# Sheet1-IR-Sensor.net
KiCad netlist of a schematic drawn in Altium Designer
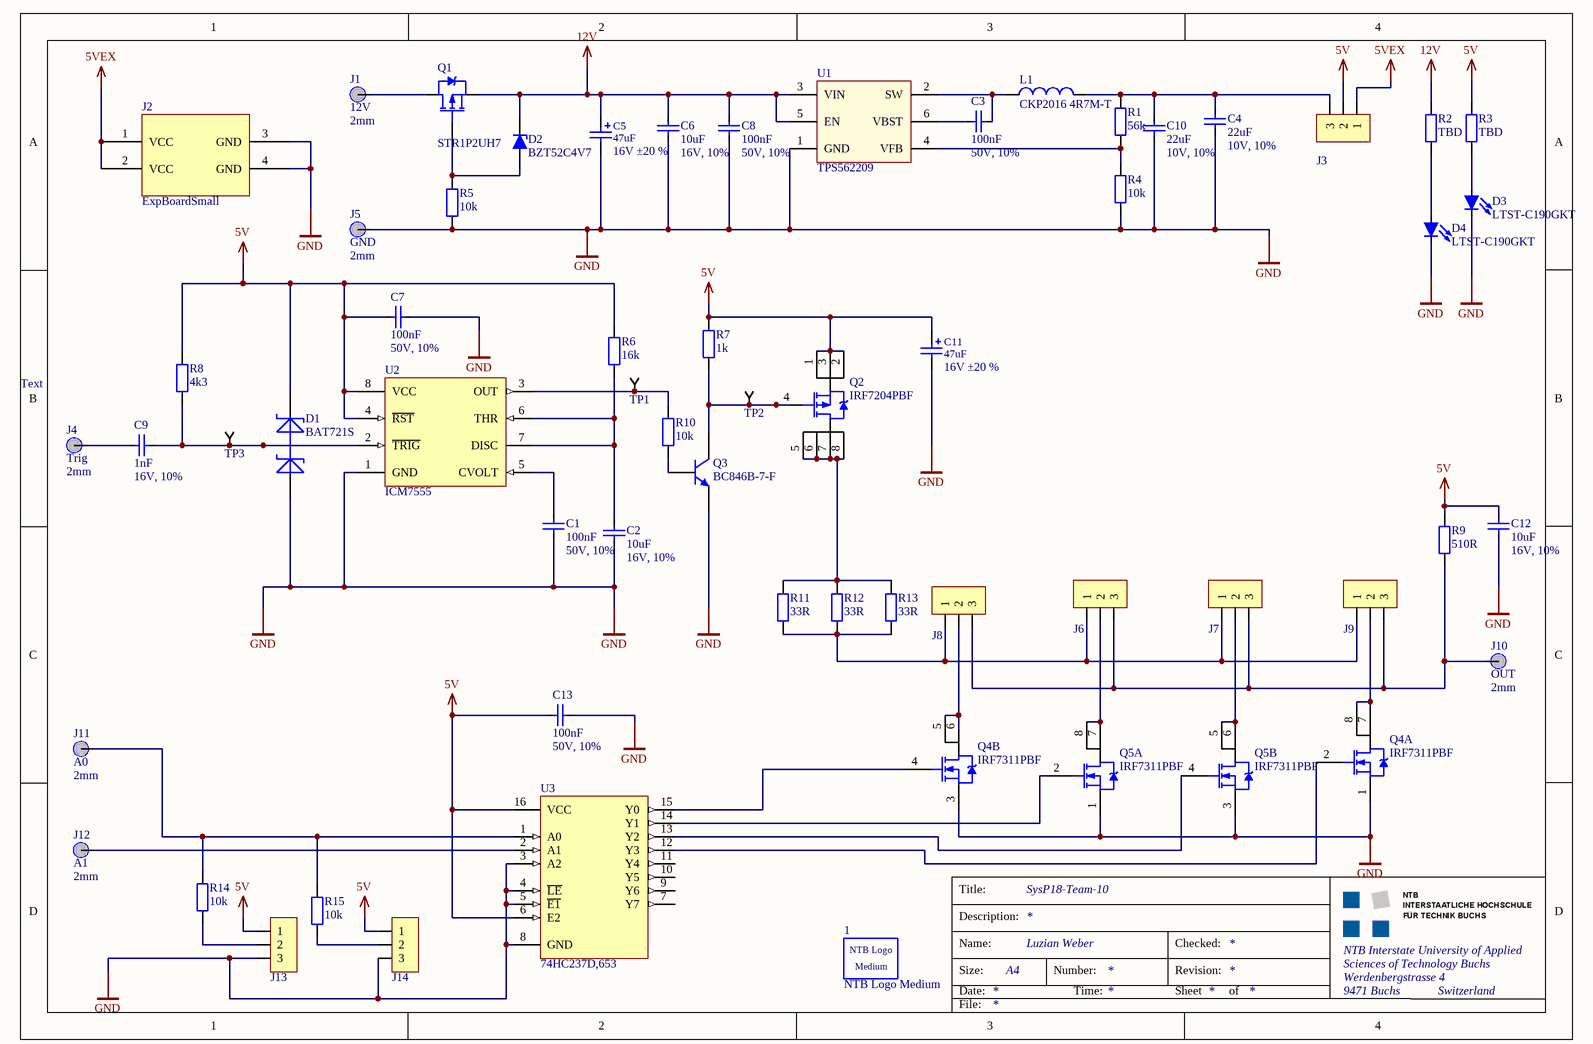
[diagram p0: Sheet1-IR-Sensor.SchDoc]

(export (version "E")
  (design (tool "Eeschema 10.0.6"))
  (components
    (comp (ref "1")
      (value "NTB Logo Medium")
      (footprint "NTB Logo Medium Copper")
      (libsource (lib "IR-Sensor") (part "NTB Logo Medium Copper"))
    )
    (comp (ref "C1")
      (value "100nF")
      (footprint "CAP-0805[2012]")
      (description "100n 50V X7R MLCC 0805 (1608 Metric)")
      (fields (field (name "TOLERANCE") "10%") (field (name "VALADDON") "50V, 10%"))
      (libsource (lib "IR-Sensor") (part "MLCC 0805 100n 50V"))
    )
    (comp (ref "C2")
      (value "10uF")
      (footprint "CAP-1206[3216]")
      (description "10u 16V X7R MLCC 1206 (3016 Metric)")
      (fields (field (name "TOLERANCE") "10%") (field (name "VALADDON") "16V, 10%"))
      (libsource (lib "IR-Sensor") (part "MLCC 1206 10u 16V"))
    )
    (comp (ref "C3")
      (value "100nF")
      (footprint "CAP-0805[2012]")
      (description "100n 50V X7R MLCC 0805 (1608 Metric)")
      (fields (field (name "TOLERANCE") "10%") (field (name "VALADDON") "50V, 10%"))
      (libsource (lib "IR-Sensor") (part "MLCC 0805 100n 50V"))
    )
    (comp (ref "C4")
      (value "22uF")
      (footprint "CAP-1206[3216]")
      (description "22u 10V X7R MLCC 1206 (3016 Metric)")
      (fields (field (name "TOLERANCE") "10%") (field (name "VALADDON") "10V, 10%"))
      (libsource (lib "IR-Sensor") (part "MLCC 1206 22u 10V"))
    )
    (comp (ref "C5")
      (value "47uF")
      (footprint "CDE_CAP AVE CODE D_H")
      (description "ELKO, 47uF, 16V, CDE_AVE476M16D16T-F_AVE CODE D")
      (fields
        (field (name "MANUFACTURER") "Cornell Dubilier")
        (field (name "VALUEADDON") "16V ±20 %")
        (field (name "Comment") "AVE476M16D16T-F")
        (field (name "PUBLISHER") "Stefan Ursella, M.Eng")
      )
      (libsource (lib "IR-Sensor") (part "ELKO 47uF 16V"))
    )
    (comp (ref "C6")
      (value "10uF")
      (footprint "CAP-1206[3216]")
      (description "10u 16V X7R MLCC 1206 (3016 Metric)")
      (fields (field (name "TOLERANCE") "10%") (field (name "VALADDON") "16V, 10%"))
      (libsource (lib "IR-Sensor") (part "MLCC 1206 10u 16V"))
    )
    (comp (ref "C7")
      (value "100nF")
      (footprint "CAP-0805[2012]")
      (description "100n 50V X7R MLCC 0805 (1608 Metric)")
      (fields (field (name "TOLERANCE") "10%") (field (name "VALADDON") "50V, 10%"))
      (libsource (lib "IR-Sensor") (part "MLCC 0805 100n 50V"))
    )
    (comp (ref "C8")
      (value "100nF")
      (footprint "CAP-0805[2012]")
      (description "100n 50V X7R MLCC 0805 (1608 Metric)")
      (fields (field (name "TOLERANCE") "10%") (field (name "VALADDON") "50V, 10%"))
      (libsource (lib "IR-Sensor") (part "MLCC 0805 100n 50V"))
    )
    (comp (ref "C9")
      (value "1nF")
      (footprint "CAP-0805[2012]")
      (description "MLCC - SMD/SMT 0805 1000pF 16V C0G 10%")
      (fields
        (field (name "MANUFACTURER") "Vishay")
        (field (name "VALUEADDON") "16V, 10%")
        (field (name "PUBLISHER") "SCLM")
      )
      (libsource (lib "IR-Sensor") (part "MLCC 0805 1n 16V"))
    )
    (comp (ref "C10")
      (value "22uF")
      (footprint "CAP-1206[3216]")
      (description "22u 10V X7R MLCC 1206 (3016 Metric)")
      (fields (field (name "TOLERANCE") "10%") (field (name "VALADDON") "10V, 10%"))
      (libsource (lib "IR-Sensor") (part "MLCC 1206 22u 10V"))
    )
    (comp (ref "C11")
      (value "47uF")
      (footprint "CDE_CAP AVE CODE D_H")
      (description "ELKO, 47uF, 16V, CDE_AVE476M16D16T-F_AVE CODE D")
      (fields
        (field (name "MANUFACTURER") "Cornell Dubilier")
        (field (name "VALUEADDON") "16V ±20 %")
        (field (name "Comment") "AVE476M16D16T-F")
        (field (name "PUBLISHER") "Stefan Ursella, M.Eng")
      )
      (libsource (lib "IR-Sensor") (part "ELKO 47uF 16V"))
    )
    (comp (ref "C12")
      (value "10uF")
      (footprint "CAP-1206[3216]")
      (description "10u 16V X7R MLCC 1206 (3016 Metric)")
      (fields (field (name "TOLERANCE") "10%") (field (name "VALADDON") "16V, 10%"))
      (libsource (lib "IR-Sensor") (part "MLCC 1206 10u 16V"))
    )
    (comp (ref "C13")
      (value "100nF")
      (footprint "CAP-0805[2012]")
      (description "100n 50V X7R MLCC 0805 (1608 Metric)")
      (fields (field (name "TOLERANCE") "10%") (field (name "VALADDON") "50V, 10%"))
      (libsource (lib "IR-Sensor") (part "MLCC 0805 100n 50V"))
    )
    (comp (ref "D1")
      (value "BAT721S")
      (footprint "SOT-23")
      (description "NXP  BAT721S  SCHOTTKY-DIODE, 2FACH")
      (fields (field (name "MANUFACTURER") "NXP") (field (name "PUBLISHER") "SCNP"))
      (libsource (lib "IR-Sensor") (part "BAT721S-SOT23"))
    )
    (comp (ref "D2")
      (value "BZT52C4V7")
      (footprint "SOD-123")
      (description "4.7V Zener-Diode, BZT52C4V7")
      (libsource (lib "IR-Sensor") (part "BZT52C4V7"))
    )
    (comp (ref "D3")
      (value "LTST-C190GKT")
      (footprint "LED 0603 green")
      (description "LED SMD 0603 green 6mcd")
      (libsource (lib "IR-Sensor") (part "LED Green"))
    )
    (comp (ref "D4")
      (value "LTST-C190GKT")
      (footprint "LED 0603 green")
      (description "LED SMD 0603 green 6mcd")
      (libsource (lib "IR-Sensor") (part "LED Green"))
    )
    (comp (ref "J1")
      (value "12V")
      (footprint "Laborbuchse 2mm")
      (description "Laborbuchse")
      (fields (field (name "SIZE") "2mm") (field (name "PUBLISHER") "B.Sc. Ursella"))
      (libsource (lib "IR-Sensor") (part "Laborbuchse"))
    )
    (comp (ref "J2")
      (value "ExpBoardSmall")
      (footprint "EXPBOARDCON")
      (libsource (lib "IR-Sensor") (part "ExpBoardSmall"))
    )
    (comp (ref "J3")
      (value "3 Pin Header")
      (footprint "3PIN HEADER 2.54MM")
      (description "3 Pin Header 2.54mm")
      (fields (field (name "PUBLISHER") "SCLM"))
      (libsource (lib "") (part "3 Pin Header_1"))
    )
    (comp (ref "J4")
      (value "Trig")
      (footprint "Laborbuchse 2mm")
      (description "Laborbuchse")
      (fields (field (name "SIZE") "2mm") (field (name "PUBLISHER") "B.Sc. Ursella"))
      (libsource (lib "IR-Sensor") (part "Laborbuchse"))
    )
    (comp (ref "J5")
      (value "GND")
      (footprint "Laborbuchse 2mm")
      (description "Laborbuchse")
      (fields (field (name "SIZE") "2mm") (field (name "PUBLISHER") "B.Sc. Ursella"))
      (libsource (lib "IR-Sensor") (part "Laborbuchse"))
    )
    (comp (ref "J6")
      (value "3 Pin Header Buchse")
      (footprint "3PIN HEADER SOCKET 2.54MM")
      (description "3 Pin Header 2.54mm Buchse")
      (libsource (lib "IR-Sensor") (part "3 Pin Header Buchse"))
    )
    (comp (ref "J7")
      (value "3 Pin Header Buchse")
      (footprint "3PIN HEADER SOCKET 2.54MM")
      (description "3 Pin Header 2.54mm Buchse")
      (libsource (lib "IR-Sensor") (part "3 Pin Header Buchse"))
    )
    (comp (ref "J8")
      (value "3 Pin Header Buchse")
      (footprint "3PIN HEADER SOCKET 2.54MM")
      (description "3 Pin Header 2.54mm Buchse")
      (libsource (lib "IR-Sensor") (part "3 Pin Header Buchse"))
    )
    (comp (ref "J9")
      (value "3 Pin Header Buchse")
      (footprint "3PIN HEADER SOCKET 2.54MM")
      (description "3 Pin Header 2.54mm Buchse")
      (libsource (lib "IR-Sensor") (part "3 Pin Header Buchse"))
    )
    (comp (ref "J10")
      (value "OUT")
      (footprint "Laborbuchse 2mm")
      (description "Laborbuchse")
      (fields (field (name "SIZE") "2mm") (field (name "PUBLISHER") "B.Sc. Ursella"))
      (libsource (lib "") (part "Laborbuchse_1"))
    )
    (comp (ref "J11")
      (value "A0")
      (footprint "Laborbuchse 2mm")
      (description "Laborbuchse")
      (fields (field (name "SIZE") "2mm") (field (name "PUBLISHER") "B.Sc. Ursella"))
      (libsource (lib "IR-Sensor") (part "Laborbuchse"))
    )
    (comp (ref "J12")
      (value "A1")
      (footprint "Laborbuchse 2mm")
      (description "Laborbuchse")
      (fields (field (name "SIZE") "2mm") (field (name "PUBLISHER") "B.Sc. Ursella"))
      (libsource (lib "IR-Sensor") (part "Laborbuchse"))
    )
    (comp (ref "J13")
      (value "3 Pin Header")
      (footprint "3PIN HEADER 2.54MM")
      (description "3 Pin Header 2.54mm")
      (fields (field (name "PUBLISHER") "SCLM"))
      (libsource (lib "IR-Sensor") (part "3 Pin Header"))
    )
    (comp (ref "J14")
      (value "3 Pin Header")
      (footprint "3PIN HEADER 2.54MM")
      (description "3 Pin Header 2.54mm")
      (fields (field (name "PUBLISHER") "SCLM"))
      (libsource (lib "IR-Sensor") (part "3 Pin Header"))
    )
    (comp (ref "L1")
      (value "CKP2016 4R7M-T")
      (footprint "IND-0806")
      (description "MULTILAYER CHIP POWER INDUCTORS")
      (libsource (lib "IR-Sensor") (part "L 4.7u"))
    )
    (comp (ref "Q1")
      (value "STR1P2UH7")
      (footprint "SOT-23")
      (description "Low Power P-Kanal Mosfet")
      (fields (field (name "MANUFACTURER") "ST Microelectronics"))
      (libsource (lib "IR-Sensor") (part "STR1P2UH7"))
    )
    (comp (ref "Q2")
      (value "IRF7204PBF")
      (footprint "SOIC-8")
      (description "High Power P-Kanal Mosfet")
      (fields
        (field (name "MANUFACTURER") "International Rectifiers")
        (field (name "PUBLISHER") "Altium Limited")
      )
      (libsource (lib "IR-Sensor") (part "IRF7204"))
    )
    (comp (ref "Q3")
      (value "BC846B-7-F")
      (footprint "SOT-23")
      (description "NPN General-purpose Transistor")
      (fields (field (name "MANUFACTURER") "DIODES INC") (field (name "PUBLISHER") "Altium Limited"))
      (libsource (lib "IR-Sensor") (part "BC846B-SOT23"))
    )
    (comp (ref "Q4")
      (value "IRF7311PBF")
      (footprint "SOIC-8")
      (description "Dual N-Kanal Mosfet")
      (fields
        (field (name "MANUFACTURER") "International Rectifier")
        (field (name "PUBLISHER") "Altium Limited")
      )
      (libsource (lib "IR-Sensor") (part "IRF7311"))
    )
    (comp (ref "Q5")
      (value "IRF7311PBF")
      (footprint "SOIC-8")
      (description "Dual N-Kanal Mosfet")
      (fields
        (field (name "MANUFACTURER") "International Rectifier")
        (field (name "PUBLISHER") "Altium Limited")
      )
      (libsource (lib "IR-Sensor") (part "IRF7311"))
    )
    (comp (ref "R1")
      (value "56k")
      (footprint "RES-0603[1608]")
      (description "0603 (1608 Metric) 1/10 W 10K 1 Thick Film Chip Resistor")
      (fields (field (name "POWER") "1/10 W") (field (name "TOLERANCE") "1%"))
      (libsource (lib "IR-Sensor") (part "RES 0603"))
    )
    (comp (ref "R2")
      (value "TBD")
      (footprint "RES-0603[1608]")
      (description "0603 (1608 Metric) 1/10 W 10K 1 Thick Film Chip Resistor")
      (fields (field (name "POWER") "1/10 W") (field (name "TOLERANCE") "1%"))
      (libsource (lib "IR-Sensor") (part "RES 0603"))
    )
    (comp (ref "R3")
      (value "TBD")
      (footprint "RES-0603[1608]")
      (description "0603 (1608 Metric) 1/10 W 10K 1 Thick Film Chip Resistor")
      (fields (field (name "POWER") "1/10 W") (field (name "TOLERANCE") "1%"))
      (libsource (lib "IR-Sensor") (part "RES 0603"))
    )
    (comp (ref "R4")
      (value "10k")
      (footprint "RES-0603[1608]")
      (description "0603 (1608 Metric) 1/10 W 10K 1 Thick Film Chip Resistor")
      (fields (field (name "POWER") "1/10 W") (field (name "TOLERANCE") "1%"))
      (libsource (lib "IR-Sensor") (part "RES 0603"))
    )
    (comp (ref "R5")
      (value "10k")
      (footprint "RES-0603[1608]")
      (description "0603 (1608 Metric) 1/10 W 10K 1 Thick Film Chip Resistor")
      (fields (field (name "POWER") "1/10 W") (field (name "TOLERANCE") "1%"))
      (libsource (lib "IR-Sensor") (part "RES 0603"))
    )
    (comp (ref "R6")
      (value "16k")
      (footprint "RES-0805[2012]")
      (description "0805 (2013 Metric) 1/10 W 10K 1 Thick Film Chip Resistor")
      (fields (field (name "POWER") "1/10 W") (field (name "TOLERANCE") "1%"))
      (libsource (lib "IR-Sensor") (part "RES 0805"))
    )
    (comp (ref "R7")
      (value "1k")
      (footprint "RES-0805[2012]")
      (description "0805 (2013 Metric) 1/10 W 10K 1 Thick Film Chip Resistor")
      (fields (field (name "POWER") "1/10 W") (field (name "TOLERANCE") "1%"))
      (libsource (lib "IR-Sensor") (part "RES 0805"))
    )
    (comp (ref "R8")
      (value "4k3")
      (footprint "RES-0805[2012]")
      (description "0805 (2013 Metric) 1/10 W 10K 1 Thick Film Chip Resistor")
      (fields (field (name "POWER") "1/10 W") (field (name "TOLERANCE") "1%"))
      (libsource (lib "IR-Sensor") (part "RES 0805"))
    )
    (comp (ref "R9")
      (value "510R")
      (footprint "RES-0805[2012]")
      (description "0805 (2013 Metric) 1/10 W 10K 1 Thick Film Chip Resistor")
      (fields (field (name "POWER") "1/10 W") (field (name "TOLERANCE") "1%"))
      (libsource (lib "IR-Sensor") (part "RES 0805"))
    )
    (comp (ref "R10")
      (value "10k")
      (footprint "RES-0805[2012]")
      (description "0805 (2013 Metric) 1/10 W 10K 1 Thick Film Chip Resistor")
      (fields (field (name "POWER") "1/10 W") (field (name "TOLERANCE") "1%"))
      (libsource (lib "IR-Sensor") (part "RES 0805"))
    )
    (comp (ref "R11")
      (value "33R")
      (footprint "RES-0805[2012]")
      (description "0805 (2013 Metric) 1/10 W 10K 1 Thick Film Chip Resistor")
      (fields (field (name "POWER") "1/10 W") (field (name "TOLERANCE") "1%"))
      (libsource (lib "IR-Sensor") (part "RES 0805"))
    )
    (comp (ref "R12")
      (value "33R")
      (footprint "RES-0805[2012]")
      (description "0805 (2013 Metric) 1/10 W 10K 1 Thick Film Chip Resistor")
      (fields (field (name "POWER") "1/10 W") (field (name "TOLERANCE") "1%"))
      (libsource (lib "IR-Sensor") (part "RES 0805"))
    )
    (comp (ref "R13")
      (value "33R")
      (footprint "RES-0805[2012]")
      (description "0805 (2013 Metric) 1/10 W 10K 1 Thick Film Chip Resistor")
      (fields (field (name "POWER") "1/10 W") (field (name "TOLERANCE") "1%"))
      (libsource (lib "IR-Sensor") (part "RES 0805"))
    )
    (comp (ref "R14")
      (value "10k")
      (footprint "RES-0805[2012]")
      (description "0805 (2013 Metric) 1/10 W 10K 1 Thick Film Chip Resistor")
      (fields (field (name "POWER") "1/10 W") (field (name "TOLERANCE") "1%"))
      (libsource (lib "IR-Sensor") (part "RES 0805"))
    )
    (comp (ref "R15")
      (value "10k")
      (footprint "RES-0805[2012]")
      (description "0805 (2013 Metric) 1/10 W 10K 1 Thick Film Chip Resistor")
      (fields (field (name "POWER") "1/10 W") (field (name "TOLERANCE") "1%"))
      (libsource (lib "IR-Sensor") (part "RES 0805"))
    )
    (comp (ref "TP1")
      (value "Testpoint SMD 1206")
      (footprint "TP-SMD-1206")
      (description "Testpoint xSmall")
      (libsource (lib "IR-Sensor") (part "Testpoint SMD 1206"))
    )
    (comp (ref "TP2")
      (value "Testpunkt THT 1mm")
      (footprint "TP-THT-1.1mm")
      (fields (field (name "MANUFACTURER") "Keystone Electronics") (field (name "PUBLISHER") "B.Sc. Ursella"))
      (libsource (lib "IR-Sensor") (part "Testpunkt THT 1mm"))
    )
    (comp (ref "TP3")
      (value "Testpunkt THT 1mm")
      (footprint "TP-THT-1.1mm")
      (fields (field (name "MANUFACTURER") "Keystone Electronics") (field (name "PUBLISHER") "B.Sc. Ursella"))
      (libsource (lib "IR-Sensor") (part "Testpunkt THT 1mm"))
    )
    (comp (ref "U1")
      (value "TPS562209")
      (footprint "SOT-23-6")
      (description "3-A Synchronous Step-Down Voltage Regulator")
      (libsource (lib "IR-Sensor") (part "TPS562209-SOT23-6"))
    )
    (comp (ref "U2")
      (value "ICM7555")
      (footprint "SOIC-8")
      (description "General purpose CMOS timer")
      (fields
        (field (name "MANUFACTURER") "National Semiconductor")
        (field (name "PUBLISHER") "Altium Hobart Technology Centre")
      )
      (libsource (lib "IR-Sensor") (part "ICM7555-SOIC8"))
    )
    (comp (ref "U3")
      (value "74HC237D,653")
      (footprint "SOIC-16")
      (description "3-to-8 line decoder, demultiplexer, NXP, SO16")
      (fields (field (name "MANUFACTURER") "NXP") (field (name "PUBLISHER") "SCLM"))
      (libsource (lib "IR-Sensor") (part "74HC237D-SOIC16"))
    )
  )
  (nets
    (net (code "1") (name "5V") (class "Default")
      (node (ref "C11") (pin "1") (pinfunction "Pos_1") (pintype "passive"))
      (node (ref "C12") (pin "1") (pinfunction "Pos_1") (pintype "passive"))
      (node (ref "C13") (pin "1") (pinfunction "Pos_1") (pintype "passive"))
      (node (ref "C7") (pin "1") (pinfunction "Pos_1") (pintype "passive"))
      (node (ref "D1") (pin "2") (pinfunction "cathode2_2") (pintype "passive"))
      (node (ref "J13") (pin "1") (pinfunction "1_1") (pintype "passive"))
      (node (ref "J14") (pin "1") (pinfunction "1_1") (pintype "passive"))
      (node (ref "J3") (pin "2") (pinfunction "2_2") (pintype "passive"))
      (node (ref "Q2") (pin "1") (pinfunction "S_1") (pintype "passive"))
      (node (ref "Q2") (pin "2") (pinfunction "S_2") (pintype "passive"))
      (node (ref "Q2") (pin "3") (pinfunction "S_3") (pintype "passive"))
      (node (ref "R3") (pin "2") (pinfunction "2_2") (pintype "passive"))
      (node (ref "R6") (pin "2") (pinfunction "2_2") (pintype "passive"))
      (node (ref "R7") (pin "2") (pinfunction "2_2") (pintype "passive"))
      (node (ref "R8") (pin "2") (pinfunction "2_2") (pintype "passive"))
      (node (ref "R9") (pin "2") (pinfunction "2_2") (pintype "passive"))
      (node (ref "U2") (pin "4") (pinfunction "~{RST}_4") (pintype "input"))
      (node (ref "U2") (pin "8") (pinfunction "VCC_8") (pintype "power_in"))
      (node (ref "U3") (pin "16") (pinfunction "VCC_16") (pintype "power_in"))
      (node (ref "U3") (pin "6") (pinfunction "E2_6") (pintype "input"))
    )
    (net (code "2") (name "5VEX") (class "Default")
      (node (ref "J2") (pin "1") (pinfunction "VCC_1") (pintype "passive"))
      (node (ref "J2") (pin "2") (pinfunction "VCC_2") (pintype "passive"))
      (node (ref "J3") (pin "1") (pinfunction "1_1") (pintype "passive"))
    )
    (net (code "3") (name "12V") (class "Default")
      (node (ref "C5") (pin "1") (pinfunction "Pos_1") (pintype "passive"))
      (node (ref "C6") (pin "1") (pinfunction "Pos_1") (pintype "passive"))
      (node (ref "C8") (pin "1") (pinfunction "Pos_1") (pintype "passive"))
      (node (ref "D2") (pin "1") (pinfunction "K_1") (pintype "passive"))
      (node (ref "Q1") (pin "2") (pinfunction "S_2") (pintype "passive"))
      (node (ref "R2") (pin "2") (pinfunction "2_2") (pintype "passive"))
      (node (ref "U1") (pin "3") (pinfunction "VIN_3") (pintype "passive"))
      (node (ref "U1") (pin "5") (pinfunction "EN_5") (pintype "passive"))
    )
    (net (code "4") (name "GND") (class "Default")
      (node (ref "C1") (pin "2") (pinfunction "Neg_2") (pintype "passive"))
      (node (ref "C10") (pin "2") (pinfunction "Neg_2") (pintype "passive"))
      (node (ref "C11") (pin "2") (pinfunction "Neg_2") (pintype "passive"))
      (node (ref "C12") (pin "2") (pinfunction "Neg_2") (pintype "passive"))
      (node (ref "C13") (pin "2") (pinfunction "Neg_2") (pintype "passive"))
      (node (ref "C2") (pin "2") (pinfunction "Neg_2") (pintype "passive"))
      (node (ref "C4") (pin "2") (pinfunction "Neg_2") (pintype "passive"))
      (node (ref "C5") (pin "2") (pinfunction "Neg_2") (pintype "passive"))
      (node (ref "C6") (pin "2") (pinfunction "Neg_2") (pintype "passive"))
      (node (ref "C7") (pin "2") (pinfunction "Neg_2") (pintype "passive"))
      (node (ref "C8") (pin "2") (pinfunction "Neg_2") (pintype "passive"))
      (node (ref "D1") (pin "1") (pinfunction "Anode1_1") (pintype "passive"))
      (node (ref "D3") (pin "1") (pinfunction "K_1") (pintype "passive"))
      (node (ref "D4") (pin "1") (pinfunction "K_1") (pintype "passive"))
      (node (ref "J13") (pin "3") (pinfunction "3_3") (pintype "passive"))
      (node (ref "J14") (pin "3") (pinfunction "3_3") (pintype "passive"))
      (node (ref "J2") (pin "3") (pinfunction "GND_3") (pintype "passive"))
      (node (ref "J2") (pin "4") (pinfunction "GND_4") (pintype "passive"))
      (node (ref "J5") (pin "1") (pinfunction "1_1") (pintype "passive"))
      (node (ref "Q3") (pin "2") (pinfunction "E_2") (pintype "passive"))
      (node (ref "Q4") (pin "1") (pinfunction "S_1") (pintype "passive"))
      (node (ref "Q4") (pin "3") (pinfunction "S_3") (pintype "passive"))
      (node (ref "Q5") (pin "1") (pinfunction "S_1") (pintype "passive"))
      (node (ref "Q5") (pin "3") (pinfunction "S_3") (pintype "passive"))
      (node (ref "R4") (pin "1") (pinfunction "1_1") (pintype "passive"))
      (node (ref "R5") (pin "1") (pinfunction "1_1") (pintype "passive"))
      (node (ref "U1") (pin "1") (pinfunction "GND_1") (pintype "passive"))
      (node (ref "U2") (pin "1") (pinfunction "GND_1") (pintype "power_in"))
      (node (ref "U3") (pin "3") (pinfunction "A2_3") (pintype "input"))
      (node (ref "U3") (pin "4") (pinfunction "LE_4") (pintype "input"))
      (node (ref "U3") (pin "5") (pinfunction "E1_5") (pintype "input"))
      (node (ref "U3") (pin "8") (pinfunction "GND_8") (pintype "power_in"))
    )
    (net (code "5") (name "Net-(C1-Pos)") (class "Default")
      (node (ref "C1") (pin "1") (pinfunction "Pos_1") (pintype "passive"))
      (node (ref "U2") (pin "5") (pinfunction "CVOLT_5") (pintype "input"))
    )
    (net (code "6") (name "Net-(C2-Pos)") (class "Default")
      (node (ref "C2") (pin "1") (pinfunction "Pos_1") (pintype "passive"))
      (node (ref "R6") (pin "1") (pinfunction "1_1") (pintype "passive"))
      (node (ref "U2") (pin "6") (pinfunction "THR_6") (pintype "input"))
      (node (ref "U2") (pin "7") (pinfunction "DISC_7") (pintype "open_collector"))
    )
    (net (code "7") (name "Net-(C3-Neg)") (class "Default")
      (node (ref "C3") (pin "2") (pinfunction "Neg_2") (pintype "passive"))
      (node (ref "L1") (pin "1") (pinfunction "1_1") (pintype "passive"))
      (node (ref "U1") (pin "2") (pinfunction "SW_2") (pintype "passive"))
    )
    (net (code "8") (name "Net-(C3-Pos)") (class "Default")
      (node (ref "C3") (pin "1") (pinfunction "Pos_1") (pintype "passive"))
      (node (ref "U1") (pin "6") (pinfunction "VBST_6") (pintype "passive"))
    )
    (net (code "9") (name "Net-(C9-Neg)") (class "Default")
      (node (ref "C9") (pin "2") (pinfunction "Neg_2") (pintype "passive"))
      (node (ref "D1") (pin "3") (pinfunction "Cathode1,_anode2_3") (pintype "passive"))
      (node (ref "R8") (pin "1") (pinfunction "1_1") (pintype "passive"))
      (node (ref "TP3") (pin "1") (pinfunction "0_1") (pintype "passive"))
      (node (ref "U2") (pin "2") (pinfunction "TRIG_2") (pintype "input"))
    )
    (net (code "10") (name "Net-(C9-Pos)") (class "Default")
      (node (ref "C9") (pin "1") (pinfunction "Pos_1") (pintype "passive"))
      (node (ref "J4") (pin "1") (pinfunction "1_1") (pintype "passive"))
    )
    (net (code "11") (name "Net-(C10-Pos)") (class "Default")
      (node (ref "C10") (pin "1") (pinfunction "Pos_1") (pintype "passive"))
      (node (ref "C4") (pin "1") (pinfunction "Pos_1") (pintype "passive"))
      (node (ref "J3") (pin "3") (pinfunction "3_3") (pintype "passive"))
      (node (ref "L1") (pin "2") (pinfunction "2_2") (pintype "passive"))
      (node (ref "R1") (pin "2") (pinfunction "2_2") (pintype "passive"))
    )
    (net (code "12") (name "Net-(D2-A)") (class "Default")
      (node (ref "D2") (pin "2") (pinfunction "A_2") (pintype "passive"))
      (node (ref "Q1") (pin "1") (pinfunction "G_1") (pintype "passive"))
      (node (ref "R5") (pin "2") (pinfunction "2_2") (pintype "passive"))
    )
    (net (code "13") (name "Net-(D3-A)") (class "Default")
      (node (ref "D3") (pin "2") (pinfunction "A_2") (pintype "passive"))
      (node (ref "R3") (pin "1") (pinfunction "1_1") (pintype "passive"))
    )
    (net (code "14") (name "Net-(D4-A)") (class "Default")
      (node (ref "D4") (pin "2") (pinfunction "A_2") (pintype "passive"))
      (node (ref "R2") (pin "1") (pinfunction "1_1") (pintype "passive"))
    )
    (net (code "15") (name "Net-(J6-Pad1)") (class "Default")
      (node (ref "J6") (pin "1") (pinfunction "1_1") (pintype "passive"))
      (node (ref "J7") (pin "1") (pinfunction "1_1") (pintype "passive"))
      (node (ref "J8") (pin "1") (pinfunction "1_1") (pintype "passive"))
      (node (ref "J9") (pin "1") (pinfunction "1_1") (pintype "passive"))
      (node (ref "R11") (pin "1") (pinfunction "1_1") (pintype "passive"))
      (node (ref "R12") (pin "1") (pinfunction "1_1") (pintype "passive"))
      (node (ref "R13") (pin "1") (pinfunction "1_1") (pintype "passive"))
    )
    (net (code "16") (name "Net-(J6-Pad2)") (class "Default")
      (node (ref "J6") (pin "2") (pinfunction "2_2") (pintype "passive"))
      (node (ref "Q5") (pin "7") (pinfunction "D_7") (pintype "passive"))
      (node (ref "Q5") (pin "8") (pinfunction "D_8") (pintype "passive"))
    )
    (net (code "17") (name "Net-(J7-Pad2)") (class "Default")
      (node (ref "J7") (pin "2") (pinfunction "2_2") (pintype "passive"))
      (node (ref "Q5") (pin "5") (pinfunction "D_5") (pintype "passive"))
      (node (ref "Q5") (pin "6") (pinfunction "D_6") (pintype "passive"))
    )
    (net (code "18") (name "Net-(J8-Pad2)") (class "Default")
      (node (ref "J8") (pin "2") (pinfunction "2_2") (pintype "passive"))
      (node (ref "Q4") (pin "5") (pinfunction "D_5") (pintype "passive"))
      (node (ref "Q4") (pin "6") (pinfunction "D_6") (pintype "passive"))
    )
    (net (code "19") (name "Net-(J9-Pad2)") (class "Default")
      (node (ref "J9") (pin "2") (pinfunction "2_2") (pintype "passive"))
      (node (ref "Q4") (pin "7") (pinfunction "D_7") (pintype "passive"))
      (node (ref "Q4") (pin "8") (pinfunction "D_8") (pintype "passive"))
    )
    (net (code "20") (name "Net-(J10-Pad1)") (class "Default")
      (node (ref "J10") (pin "1") (pinfunction "1_1") (pintype "passive"))
      (node (ref "J6") (pin "3") (pinfunction "3_3") (pintype "passive"))
      (node (ref "J7") (pin "3") (pinfunction "3_3") (pintype "passive"))
      (node (ref "J8") (pin "3") (pinfunction "3_3") (pintype "passive"))
      (node (ref "J9") (pin "3") (pinfunction "3_3") (pintype "passive"))
      (node (ref "R9") (pin "1") (pinfunction "1_1") (pintype "passive"))
    )
    (net (code "21") (name "Net-(J13-Pad2)") (class "Default")
      (node (ref "J13") (pin "2") (pinfunction "2_2") (pintype "passive"))
      (node (ref "R14") (pin "1") (pinfunction "1_1") (pintype "passive"))
    )
    (net (code "22") (name "Net-(J14-Pad2)") (class "Default")
      (node (ref "J14") (pin "2") (pinfunction "2_2") (pintype "passive"))
      (node (ref "R15") (pin "1") (pinfunction "1_1") (pintype "passive"))
    )
    (net (code "23") (name "Net-(Q1-D)") (class "Default")
      (node (ref "J1") (pin "1") (pinfunction "1_1") (pintype "passive"))
      (node (ref "Q1") (pin "3") (pinfunction "D_3") (pintype "passive"))
    )
    (net (code "24") (name "Net-(Q2-D-Pad5)") (class "Default")
      (node (ref "Q2") (pin "5") (pinfunction "D_5") (pintype "passive"))
      (node (ref "Q2") (pin "6") (pinfunction "D_6") (pintype "passive"))
      (node (ref "Q2") (pin "7") (pinfunction "D_7") (pintype "passive"))
      (node (ref "Q2") (pin "8") (pinfunction "D_8") (pintype "passive"))
      (node (ref "R11") (pin "2") (pinfunction "2_2") (pintype "passive"))
      (node (ref "R12") (pin "2") (pinfunction "2_2") (pintype "passive"))
      (node (ref "R13") (pin "2") (pinfunction "2_2") (pintype "passive"))
    )
    (net (code "25") (name "Net-(Q2-G)") (class "Default")
      (node (ref "Q2") (pin "4") (pinfunction "G_4") (pintype "passive"))
      (node (ref "Q3") (pin "3") (pinfunction "C_3") (pintype "passive"))
      (node (ref "R7") (pin "1") (pinfunction "1_1") (pintype "passive"))
      (node (ref "TP2") (pin "1") (pinfunction "0_1") (pintype "passive"))
    )
    (net (code "26") (name "Net-(Q3-B)") (class "Default")
      (node (ref "Q3") (pin "1") (pinfunction "B_1") (pintype "passive"))
      (node (ref "R10") (pin "1") (pinfunction "1_1") (pintype "passive"))
    )
    (net (code "27") (name "Net-(Q4A-G)") (class "Default")
      (node (ref "Q4") (pin "2") (pinfunction "G_2") (pintype "passive"))
      (node (ref "U3") (pin "12") (pinfunction "Y3_12") (pintype "output"))
    )
    (net (code "28") (name "Net-(Q4B-G)") (class "Default")
      (node (ref "Q4") (pin "4") (pinfunction "G_4") (pintype "passive"))
      (node (ref "U3") (pin "15") (pinfunction "Y0_15") (pintype "output"))
    )
    (net (code "29") (name "Net-(Q5A-G)") (class "Default")
      (node (ref "Q5") (pin "2") (pinfunction "G_2") (pintype "passive"))
      (node (ref "U3") (pin "14") (pinfunction "Y1_14") (pintype "output"))
    )
    (net (code "30") (name "Net-(Q5B-G)") (class "Default")
      (node (ref "Q5") (pin "4") (pinfunction "G_4") (pintype "passive"))
      (node (ref "U3") (pin "13") (pinfunction "Y2_13") (pintype "output"))
    )
    (net (code "31") (name "Net-(TP1-0)") (class "Default")
      (node (ref "R10") (pin "2") (pinfunction "2_2") (pintype "passive"))
      (node (ref "TP1") (pin "1") (pinfunction "0_1") (pintype "passive"))
      (node (ref "U2") (pin "3") (pinfunction "OUT_3") (pintype "output"))
    )
    (net (code "32") (name "Net-(U1-VFB)") (class "Default")
      (node (ref "R1") (pin "1") (pinfunction "1_1") (pintype "passive"))
      (node (ref "R4") (pin "2") (pinfunction "2_2") (pintype "passive"))
      (node (ref "U1") (pin "4") (pinfunction "VFB_4") (pintype "passive"))
    )
    (net (code "33") (name "Net-(U3-A0)") (class "Default")
      (node (ref "J11") (pin "1") (pinfunction "1_1") (pintype "passive"))
      (node (ref "R14") (pin "2") (pinfunction "2_2") (pintype "passive"))
      (node (ref "R15") (pin "2") (pinfunction "2_2") (pintype "passive"))
      (node (ref "U3") (pin "1") (pinfunction "A0_1") (pintype "input"))
    )
    (net (code "34") (name "Net-(U3-A1)") (class "Default")
      (node (ref "J12") (pin "1") (pinfunction "1_1") (pintype "passive"))
      (node (ref "U3") (pin "2") (pinfunction "A1_2") (pintype "input"))
    )
    (net (code "35") (name "unconnected-(U3-Y4-Pad11)") (class "Default")
      (node (ref "U3") (pin "11") (pinfunction "Y4_11") (pintype "output"))
    )
    (net (code "36") (name "unconnected-(U3-Y5-Pad10)") (class "Default")
      (node (ref "U3") (pin "10") (pinfunction "Y5_10") (pintype "output"))
    )
    (net (code "37") (name "unconnected-(U3-Y6-Pad9)") (class "Default")
      (node (ref "U3") (pin "9") (pinfunction "Y6_9") (pintype "output"))
    )
    (net (code "38") (name "unconnected-(U3-Y7-Pad7)") (class "Default")
      (node (ref "U3") (pin "7") (pinfunction "Y7_7") (pintype "output"))
    )
  )
)
